# USBHeaders.net
KiCad netlist of a schematic drawn in Altium Designer
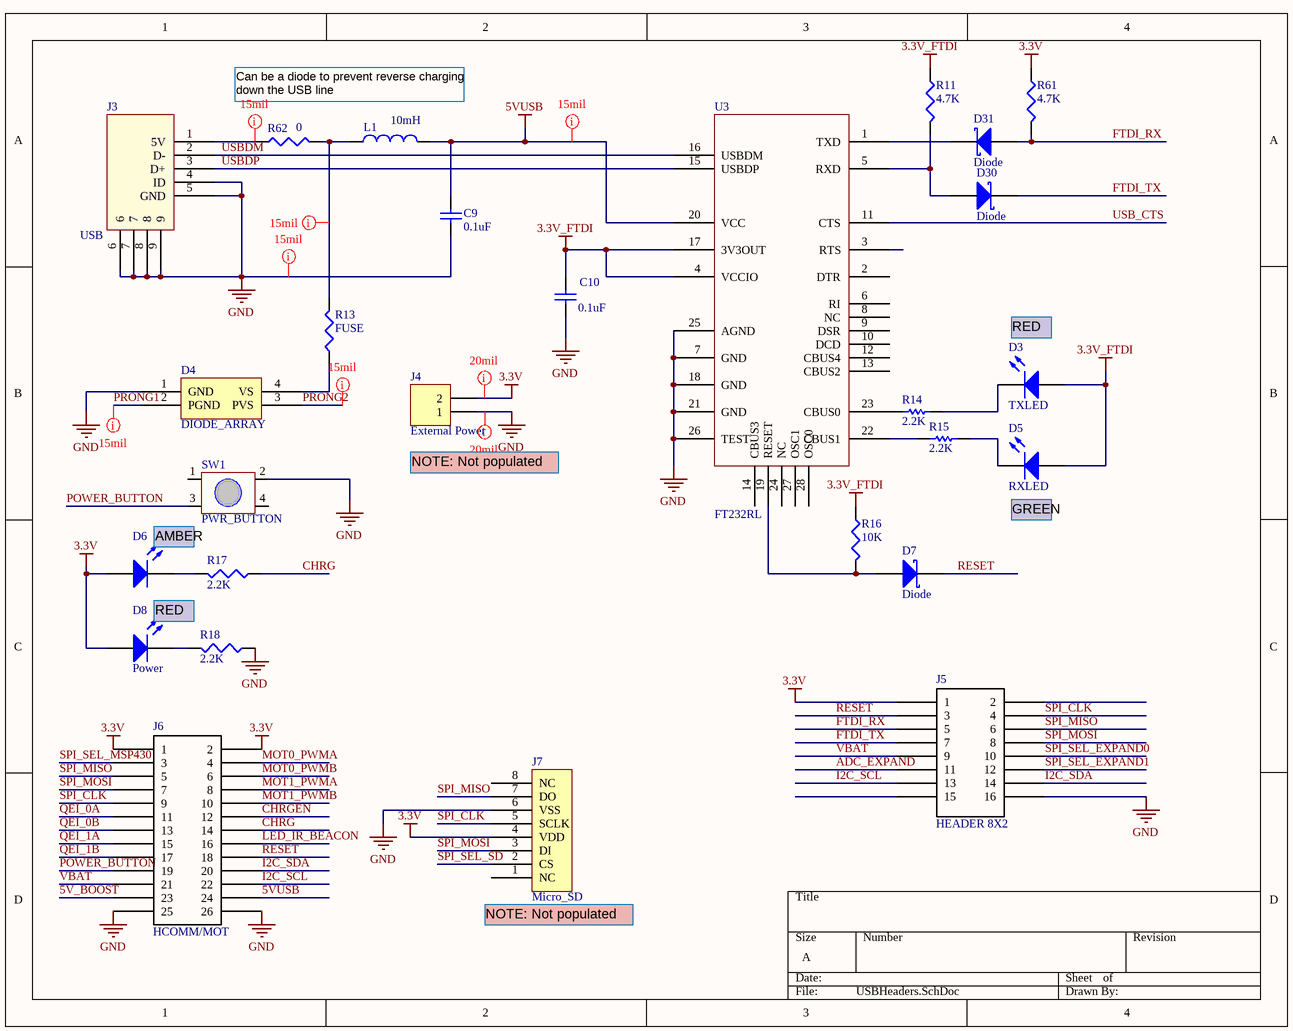
[diagram p0: USBHeaders.SchDoc]

(export (version "E")
  (design (tool "Eeschema 10.0.6"))
  (components
    (comp (ref "C9")
      (value "0.1uF")
      (footprint "CAPC1005L")
      (description "Capacitor")
      (fields (field (name "PUBLISHER") "Altium Limited"))
      (libsource (lib "Miscellaneous Devices") (part "Cap"))
    )
    (comp (ref "C10")
      (value "0.1uF")
      (footprint "CAPC1005L")
      (description "Capacitor")
      (fields (field (name "PUBLISHER") "Altium Limited"))
      (libsource (lib "Miscellaneous Devices") (part "Cap"))
    )
    (comp (ref "D3")
      (value "TXLED")
      (footprint "SurfaceMount(603)")
      (description "Typical RED, GREEN, YELLOW, AMBER GaAs LED")
      (fields (field (name "PUBLISHER") "Altium Limited"))
      (libsource (lib "Miscellaneous Devices") (part "LED2"))
    )
    (comp (ref "D4")
      (value "DIODE_ARRAY")
      (footprint "SOT143")
      (libsource (lib "mrone") (part "SCHOTTKEY_DIODE_ARRAY"))
    )
    (comp (ref "D5")
      (value "RXLED")
      (footprint "SurfaceMount(603)")
      (description "Typical RED, GREEN, YELLOW, AMBER GaAs LED")
      (fields (field (name "PUBLISHER") "Altium Limited"))
      (libsource (lib "Miscellaneous Devices") (part "LED2"))
    )
    (comp (ref "D6")
      (value "Charge")
      (footprint "SurfaceMount(603)")
      (description "Typical RED, GREEN, YELLOW, AMBER GaAs LED")
      (fields (field (name "PUBLISHER") "Altium Limited"))
      (libsource (lib "") (part "LED2_1"))
    )
    (comp (ref "D7")
      (value "Diode")
      (footprint "SurfaceMount(603)")
      (libsource (lib "mrone") (part "SchottkeyDiode"))
    )
    (comp (ref "D8") (value "Power") (footprint "SurfaceMount(603)") (libsource (lib "mrone") (part "LED")))
    (comp (ref "D30")
      (value "Diode")
      (footprint "SurfaceMount(603)")
      (libsource (lib "mrone") (part "SchottkeyDiode"))
    )
    (comp (ref "D31")
      (value "Diode")
      (footprint "SurfaceMount(603)")
      (libsource (lib "mrone") (part "SchottkeyDiode"))
    )
    (comp (ref "J3")
      (value "USB")
      (footprint "USB Minib (thru-hole)")
      (libsource (lib "mrone") (part "USB-ConnTH"))
    )
    (comp (ref "J4")
      (value "External Power")
      (footprint "HDR1X2")
      (description "Header, 2-Pin")
      (fields (field (name "PUBLISHER") "Altium Limited"))
      (libsource (lib "Miscellaneous Connectors") (part "Header 2"))
    )
    (comp (ref "J5")
      (value "HEADER 8X2")
      (footprint "HEADERSM 8X2")
      (libsource (lib "mrone") (part "HEADERS 8X2"))
    )
    (comp (ref "J6")
      (value "HCOMM/MOT")
      (footprint "HeaderSM 13x2")
      (description "Header, 2X20, 50mil, IDC")
      (libsource (lib "mrone") (part "HCOMM/HMOT"))
    )
    (comp (ref "J7") (value "Micro_SD") (footprint "MICRO_SD") (libsource (lib "mrone") (part "MICRO_SD")))
    (comp (ref "L1")
      (value "10mH")
      (footprint "INDC2012L")
      (description "Inductor")
      (fields (field (name "PUBLISHER") "Altium Limited"))
      (libsource (lib "Miscellaneous Devices") (part "Inductor"))
    )
    (comp (ref "R11")
      (value "4.7K")
      (footprint "RESC1608L")
      (description "Resistor")
      (fields (field (name "Comment") "Res3") (field (name "PUBLISHER") "Altium Limited"))
      (libsource (lib "Miscellaneous Devices") (part "Res3"))
    )
    (comp (ref "R13")
      (value "FUSE")
      (footprint "RESC3225L")
      (description "Resistor")
      (fields (field (name "Comment") "Res3") (field (name "PUBLISHER") "Altium Limited"))
      (libsource (lib "Miscellaneous Devices") (part "Res3"))
    )
    (comp (ref "R14")
      (value "2.2K")
      (footprint "RESC1608L")
      (description "Resistor")
      (fields (field (name "PUBLISHER") "Altium Limited"))
      (libsource (lib "Miscellaneous Devices") (part "Res1"))
    )
    (comp (ref "R15")
      (value "2.2K")
      (footprint "RESC1608L")
      (description "Resistor")
      (fields (field (name "PUBLISHER") "Altium Limited"))
      (libsource (lib "Miscellaneous Devices") (part "Res1"))
    )
    (comp (ref "R16")
      (value "10K")
      (footprint "RESC1608L")
      (description "Resistor")
      (fields (field (name "Comment") "Res3") (field (name "PUBLISHER") "Altium Limited"))
      (libsource (lib "Miscellaneous Devices") (part "Res3"))
    )
    (comp (ref "R17")
      (value "2.2K")
      (footprint "RESC1608L")
      (description "Resistor")
      (fields (field (name "Comment") "Res3") (field (name "PUBLISHER") "Altium Limited"))
      (libsource (lib "Miscellaneous Devices") (part "Res3"))
    )
    (comp (ref "R18")
      (value "2.2K")
      (footprint "RESC1608L")
      (description "Resistor")
      (fields (field (name "Comment") "Res3") (field (name "PUBLISHER") "Altium Limited"))
      (libsource (lib "Miscellaneous Devices") (part "Res3"))
    )
    (comp (ref "R61")
      (value "4.7K")
      (footprint "RESC1608L")
      (description "Resistor")
      (fields (field (name "Comment") "Res3") (field (name "PUBLISHER") "Altium Limited"))
      (libsource (lib "Miscellaneous Devices") (part "Res3"))
    )
    (comp (ref "R62")
      (value "0")
      (footprint "RESC1608L")
      (description "Resistor")
      (fields (field (name "Comment") "Res3") (field (name "PUBLISHER") "Altium Limited"))
      (libsource (lib "Miscellaneous Devices") (part "Res3"))
    )
    (comp (ref "SW1")
      (value "PWR_BUTTON")
      (footprint "SwitchTall-TL330")
      (libsource (lib "mrone") (part "Switch-TL330"))
    )
    (comp (ref "U3") (value "FT232RL") (footprint "SSOP-28") (libsource (lib "mrone") (part "FT232RL")))
  )
  (nets
    (net (code "1") (name "/5V_BOOST") (class "Default")
      (node (ref "J6") (pin "23") (pinfunction "23_23") (pintype "passive"))
    )
    (net (code "3") (name "/ADC_EXPAND") (class "Default")
      (node (ref "J5") (pin "11") (pinfunction "11_11") (pintype "passive"))
    )
    (net (code "4") (name "/CHRG") (class "Default")
      (node (ref "J6") (pin "14") (pinfunction "14_14") (pintype "passive"))
      (node (ref "R17") (pin "1") (pinfunction "1_1") (pintype "passive"))
    )
    (net (code "5") (name "/CHRGEN") (class "Default")
      (node (ref "J6") (pin "12") (pinfunction "12_12") (pintype "passive"))
    )
    (net (code "6") (name "/FTDI_RX") (class "Default")
      (node (ref "D31") (pin "2") (pinfunction "A_2") (pintype "passive"))
      (node (ref "J5") (pin "5") (pinfunction "5_5") (pintype "passive"))
      (node (ref "R61") (pin "2") (pinfunction "2_2") (pintype "passive"))
    )
    (net (code "7") (name "/FTDI_TX") (class "Default")
      (node (ref "D30") (pin "1") (pinfunction "K_1") (pintype "passive"))
      (node (ref "J5") (pin "7") (pinfunction "7_7") (pintype "passive"))
    )
    (net (code "8") (name "/I2C_SCL") (class "Default")
      (node (ref "J5") (pin "13") (pinfunction "13_13") (pintype "passive"))
      (node (ref "J6") (pin "22") (pinfunction "22_22") (pintype "passive"))
    )
    (net (code "9") (name "/I2C_SDA") (class "Default")
      (node (ref "J5") (pin "14") (pinfunction "14_14") (pintype "passive"))
      (node (ref "J6") (pin "20") (pinfunction "20_20") (pintype "passive"))
    )
    (net (code "10") (name "/LED_IR_BEACON") (class "Default")
      (node (ref "J6") (pin "16") (pinfunction "16_16") (pintype "passive"))
    )
    (net (code "11") (name "/MOT0_PWMA") (class "Default")
      (node (ref "J6") (pin "4") (pinfunction "4_4") (pintype "passive"))
    )
    (net (code "12") (name "/MOT0_PWMB") (class "Default")
      (node (ref "J6") (pin "6") (pinfunction "6_6") (pintype "passive"))
    )
    (net (code "13") (name "/MOT1_PWMA") (class "Default")
      (node (ref "J6") (pin "8") (pinfunction "8_8") (pintype "passive"))
    )
    (net (code "14") (name "/MOT1_PWMB") (class "Default")
      (node (ref "J6") (pin "10") (pinfunction "10_10") (pintype "passive"))
    )
    (net (code "15") (name "/POWER_BUTTON") (class "Default")
      (node (ref "J6") (pin "19") (pinfunction "19_19") (pintype "passive"))
      (node (ref "SW1") (pin "3") (pinfunction "3_3") (pintype "passive"))
    )
    (net (code "16") (name "/PRONG1") (class "Default")
      (node (ref "D4") (pin "2") (pinfunction "PGND_2") (pintype "passive"))
    )
    (net (code "17") (name "/PRONG2") (class "Default")
      (node (ref "D4") (pin "3") (pinfunction "PVS_3") (pintype "passive"))
    )
    (net (code "18") (name "/QEI_0A") (class "Default")
      (node (ref "J6") (pin "11") (pinfunction "11_11") (pintype "passive"))
    )
    (net (code "19") (name "/QEI_0B") (class "Default")
      (node (ref "J6") (pin "13") (pinfunction "13_13") (pintype "passive"))
    )
    (net (code "20") (name "/QEI_1A") (class "Default")
      (node (ref "J6") (pin "15") (pinfunction "15_15") (pintype "passive"))
    )
    (net (code "21") (name "/QEI_1B") (class "Default")
      (node (ref "J6") (pin "17") (pinfunction "17_17") (pintype "passive"))
    )
    (net (code "22") (name "/RESET") (class "Default")
      (node (ref "D7") (pin "1") (pinfunction "K_1") (pintype "passive"))
      (node (ref "J5") (pin "3") (pinfunction "3_3") (pintype "passive"))
      (node (ref "J6") (pin "18") (pinfunction "18_18") (pintype "passive"))
    )
    (net (code "23") (name "/SPI_CLK") (class "Default")
      (node (ref "J5") (pin "4") (pinfunction "4_4") (pintype "passive"))
      (node (ref "J6") (pin "9") (pinfunction "9_9") (pintype "passive"))
      (node (ref "J7") (pin "5") (pinfunction "SCLK_5") (pintype "passive"))
    )
    (net (code "24") (name "/SPI_MISO") (class "Default")
      (node (ref "J5") (pin "6") (pinfunction "6_6") (pintype "passive"))
      (node (ref "J6") (pin "5") (pinfunction "5_5") (pintype "passive"))
      (node (ref "J7") (pin "7") (pinfunction "DO_7") (pintype "passive"))
    )
    (net (code "25") (name "/SPI_MOSI") (class "Default")
      (node (ref "J5") (pin "8") (pinfunction "8_8") (pintype "passive"))
      (node (ref "J6") (pin "7") (pinfunction "7_7") (pintype "passive"))
      (node (ref "J7") (pin "3") (pinfunction "DI_3") (pintype "passive"))
    )
    (net (code "26") (name "/SPI_SEL_EXPAND0") (class "Default")
      (node (ref "J5") (pin "10") (pinfunction "10_10") (pintype "passive"))
    )
    (net (code "27") (name "/SPI_SEL_EXPAND1") (class "Default")
      (node (ref "J5") (pin "12") (pinfunction "12_12") (pintype "passive"))
    )
    (net (code "28") (name "/SPI_SEL_MSP430") (class "Default")
      (node (ref "J6") (pin "3") (pinfunction "3_3") (pintype "passive"))
    )
    (net (code "29") (name "/SPI_SEL_SD") (class "Default")
      (node (ref "J7") (pin "2") (pinfunction "CS_2") (pintype "passive"))
    )
    (net (code "30") (name "/USBDM") (class "Default")
      (node (ref "J3") (pin "2") (pinfunction "D-_2") (pintype "passive"))
      (node (ref "U3") (pin "16") (pinfunction "USBDM_16") (pintype "passive"))
    )
    (net (code "31") (name "/USBDP") (class "Default")
      (node (ref "J3") (pin "3") (pinfunction "D+_3") (pintype "passive"))
      (node (ref "U3") (pin "15") (pinfunction "USBDP_15") (pintype "passive"))
    )
    (net (code "32") (name "/USB_CTS") (class "Default")
      (node (ref "U3") (pin "11") (pinfunction "CTS_11") (pintype "passive"))
    )
    (net (code "33") (name "/VBAT") (class "Default")
      (node (ref "J5") (pin "9") (pinfunction "9_9") (pintype "passive"))
      (node (ref "J6") (pin "21") (pinfunction "21_21") (pintype "passive"))
    )
    (net (code "34") (name "3.3V") (class "Default")
      (node (ref "D6") (pin "1") (pinfunction "A_1") (pintype "passive"))
      (node (ref "D8") (pin "1") (pinfunction "A_1") (pintype "passive"))
      (node (ref "J4") (pin "2") (pinfunction "2_2") (pintype "passive"))
      (node (ref "J5") (pin "1") (pinfunction "1_1") (pintype "passive"))
      (node (ref "J6") (pin "1") (pinfunction "1_1") (pintype "passive"))
      (node (ref "J6") (pin "2") (pinfunction "2_2") (pintype "passive"))
      (node (ref "J7") (pin "4") (pinfunction "VDD_4") (pintype "passive"))
      (node (ref "R61") (pin "1") (pinfunction "1_1") (pintype "passive"))
    )
    (net (code "35") (name "3.3V_FTDI") (class "Default")
      (node (ref "C10") (pin "2") (pinfunction "2_2") (pintype "passive"))
      (node (ref "D3") (pin "1") (pinfunction "A_1") (pintype "passive"))
      (node (ref "D5") (pin "1") (pinfunction "A_1") (pintype "passive"))
      (node (ref "R11") (pin "1") (pinfunction "1_1") (pintype "passive"))
      (node (ref "R16") (pin "1") (pinfunction "1_1") (pintype "passive"))
      (node (ref "U3") (pin "17") (pinfunction "3V3OUT_17") (pintype "passive"))
      (node (ref "U3") (pin "4") (pinfunction "VCCIO_4") (pintype "passive"))
    )
    (net (code "36") (name "5VUSB") (class "Default")
      (node (ref "C9") (pin "2") (pinfunction "2_2") (pintype "passive"))
      (node (ref "J6") (pin "24") (pinfunction "24_24") (pintype "passive"))
      (node (ref "L1") (pin "2") (pinfunction "2_2") (pintype "passive"))
      (node (ref "U3") (pin "20") (pinfunction "VCC_20") (pintype "passive"))
    )
    (net (code "37") (name "GND") (class "Default")
      (node (ref "C10") (pin "1") (pinfunction "1_1") (pintype "passive"))
      (node (ref "C9") (pin "1") (pinfunction "1_1") (pintype "passive"))
      (node (ref "D4") (pin "1") (pinfunction "GND_1") (pintype "passive"))
      (node (ref "J3") (pin "4") (pinfunction "ID_4") (pintype "passive"))
      (node (ref "J3") (pin "5") (pinfunction "GND_5") (pintype "passive"))
      (node (ref "J3") (pin "6") (pinfunction "6_6") (pintype "passive"))
      (node (ref "J3") (pin "7") (pinfunction "7_7") (pintype "passive"))
      (node (ref "J3") (pin "8") (pinfunction "8_8") (pintype "passive"))
      (node (ref "J3") (pin "9") (pinfunction "9_9") (pintype "passive"))
      (node (ref "J4") (pin "1") (pinfunction "1_1") (pintype "passive"))
      (node (ref "J5") (pin "16") (pinfunction "16_16") (pintype "passive"))
      (node (ref "J6") (pin "25") (pinfunction "25_25") (pintype "passive"))
      (node (ref "J6") (pin "26") (pinfunction "26_26") (pintype "passive"))
      (node (ref "J7") (pin "6") (pinfunction "VSS_6") (pintype "passive"))
      (node (ref "R18") (pin "1") (pinfunction "1_1") (pintype "passive"))
      (node (ref "SW1") (pin "2") (pinfunction "2_2") (pintype "passive"))
      (node (ref "U3") (pin "18") (pinfunction "GND_18") (pintype "passive"))
      (node (ref "U3") (pin "21") (pinfunction "GND_21") (pintype "passive"))
      (node (ref "U3") (pin "25") (pinfunction "AGND_25") (pintype "passive"))
      (node (ref "U3") (pin "26") (pinfunction "TEST_26") (pintype "passive"))
      (node (ref "U3") (pin "7") (pinfunction "GND_7") (pintype "passive"))
    )
    (net (code "38") (name "Net-(D3-K)") (class "Default")
      (node (ref "D3") (pin "2") (pinfunction "K_2") (pintype "passive"))
      (node (ref "R14") (pin "2") (pinfunction "2_2") (pintype "passive"))
    )
    (net (code "39") (name "Net-(D4-VS)") (class "Default")
      (node (ref "D4") (pin "4") (pinfunction "VS_4") (pintype "passive"))
      (node (ref "R13") (pin "1") (pinfunction "1_1") (pintype "passive"))
    )
    (net (code "40") (name "Net-(D5-K)") (class "Default")
      (node (ref "D5") (pin "2") (pinfunction "K_2") (pintype "passive"))
      (node (ref "R15") (pin "2") (pinfunction "2_2") (pintype "passive"))
    )
    (net (code "41") (name "Net-(D6-K)") (class "Default")
      (node (ref "D6") (pin "2") (pinfunction "K_2") (pintype "passive"))
      (node (ref "R17") (pin "2") (pinfunction "2_2") (pintype "passive"))
    )
    (net (code "42") (name "Net-(D7-A)") (class "Default")
      (node (ref "D7") (pin "2") (pinfunction "A_2") (pintype "passive"))
      (node (ref "R16") (pin "2") (pinfunction "2_2") (pintype "passive"))
      (node (ref "U3") (pin "19") (pinfunction "RESET_19") (pintype "passive"))
    )
    (net (code "43") (name "Net-(D8-K)") (class "Default")
      (node (ref "D8") (pin "2") (pinfunction "K_2") (pintype "passive"))
      (node (ref "R18") (pin "2") (pinfunction "2_2") (pintype "passive"))
    )
    (net (code "44") (name "Net-(D30-A)") (class "Default")
      (node (ref "D30") (pin "2") (pinfunction "A_2") (pintype "passive"))
      (node (ref "R11") (pin "2") (pinfunction "2_2") (pintype "passive"))
      (node (ref "U3") (pin "5") (pinfunction "RXD_5") (pintype "passive"))
    )
    (net (code "45") (name "Net-(D31-K)") (class "Default")
      (node (ref "D31") (pin "1") (pinfunction "K_1") (pintype "passive"))
      (node (ref "U3") (pin "1") (pinfunction "TXD_1") (pintype "passive"))
    )
    (net (code "46") (name "Net-(J3-5V)") (class "Default")
      (node (ref "J3") (pin "1") (pinfunction "5V_1") (pintype "passive"))
      (node (ref "R62") (pin "1") (pinfunction "1_1") (pintype "passive"))
    )
    (net (code "47") (name "Net-(L1-Pad1)") (class "Default")
      (node (ref "L1") (pin "1") (pinfunction "1_1") (pintype "passive"))
      (node (ref "R13") (pin "2") (pinfunction "2_2") (pintype "passive"))
      (node (ref "R62") (pin "2") (pinfunction "2_2") (pintype "passive"))
    )
    (net (code "48") (name "Net-(U3-CBUS0)") (class "Default")
      (node (ref "R14") (pin "1") (pinfunction "1_1") (pintype "passive"))
      (node (ref "U3") (pin "23") (pinfunction "CBUS0_23") (pintype "passive"))
    )
    (net (code "49") (name "Net-(U3-CBUS1)") (class "Default")
      (node (ref "R15") (pin "1") (pinfunction "1_1") (pintype "passive"))
      (node (ref "U3") (pin "22") (pinfunction "CBUS1_22") (pintype "passive"))
    )
    (net (code "50") (name "unconnected-(J5-Pad2)") (class "Default")
      (node (ref "J5") (pin "2") (pinfunction "2_2") (pintype "passive"))
    )
    (net (code "51") (name "unconnected-(J5-Pad15)") (class "Default")
      (node (ref "J5") (pin "15") (pinfunction "15_15") (pintype "passive"))
    )
    (net (code "52") (name "unconnected-(J7-NC-Pad1)") (class "Default")
      (node (ref "J7") (pin "1") (pinfunction "NC_1") (pintype "passive"))
    )
    (net (code "53") (name "unconnected-(J7-NC-Pad8)") (class "Default")
      (node (ref "J7") (pin "8") (pinfunction "NC_8") (pintype "passive"))
    )
    (net (code "54") (name "unconnected-(SW1-Pad1)") (class "Default")
      (node (ref "SW1") (pin "1") (pinfunction "1_1") (pintype "passive"))
    )
    (net (code "55") (name "unconnected-(SW1-Pad4)") (class "Default")
      (node (ref "SW1") (pin "4") (pinfunction "4_4") (pintype "passive"))
    )
    (net (code "56") (name "unconnected-(U3-CBUS2-Pad13)") (class "Default")
      (node (ref "U3") (pin "13") (pinfunction "CBUS2_13") (pintype "passive"))
    )
    (net (code "57") (name "unconnected-(U3-CBUS3-Pad14)") (class "Default")
      (node (ref "U3") (pin "14") (pinfunction "CBUS3_14") (pintype "passive"))
    )
    (net (code "58") (name "unconnected-(U3-CBUS4-Pad12)") (class "Default")
      (node (ref "U3") (pin "12") (pinfunction "CBUS4_12") (pintype "passive"))
    )
    (net (code "59") (name "unconnected-(U3-DCD-Pad10)") (class "Default")
      (node (ref "U3") (pin "10") (pinfunction "DCD_10") (pintype "passive"))
    )
    (net (code "60") (name "unconnected-(U3-DSR-Pad9)") (class "Default")
      (node (ref "U3") (pin "9") (pinfunction "DSR_9") (pintype "passive"))
    )
    (net (code "61") (name "unconnected-(U3-DTR-Pad2)") (class "Default")
      (node (ref "U3") (pin "2") (pinfunction "DTR_2") (pintype "passive"))
    )
    (net (code "62") (name "unconnected-(U3-NC-Pad8)") (class "Default")
      (node (ref "U3") (pin "8") (pinfunction "NC_8") (pintype "passive"))
    )
    (net (code "63") (name "unconnected-(U3-NC-Pad24)") (class "Default")
      (node (ref "U3") (pin "24") (pinfunction "NC_24") (pintype "passive"))
    )
    (net (code "64") (name "unconnected-(U3-OSC0-Pad28)") (class "Default")
      (node (ref "U3") (pin "28") (pinfunction "OSC0_28") (pintype "passive"))
    )
    (net (code "65") (name "unconnected-(U3-OSC1-Pad27)") (class "Default")
      (node (ref "U3") (pin "27") (pinfunction "OSC1_27") (pintype "passive"))
    )
    (net (code "66") (name "unconnected-(U3-RI-Pad6)") (class "Default")
      (node (ref "U3") (pin "6") (pinfunction "RI_6") (pintype "passive"))
    )
    (net (code "67") (name "unconnected-(U3-RTS-Pad3)") (class "Default")
      (node (ref "U3") (pin "3") (pinfunction "RTS_3") (pintype "passive"))
    )
  )
)
